# switch_eval_box_redo_v1.net
KiCad netlist of a schematic drawn in EAGLE
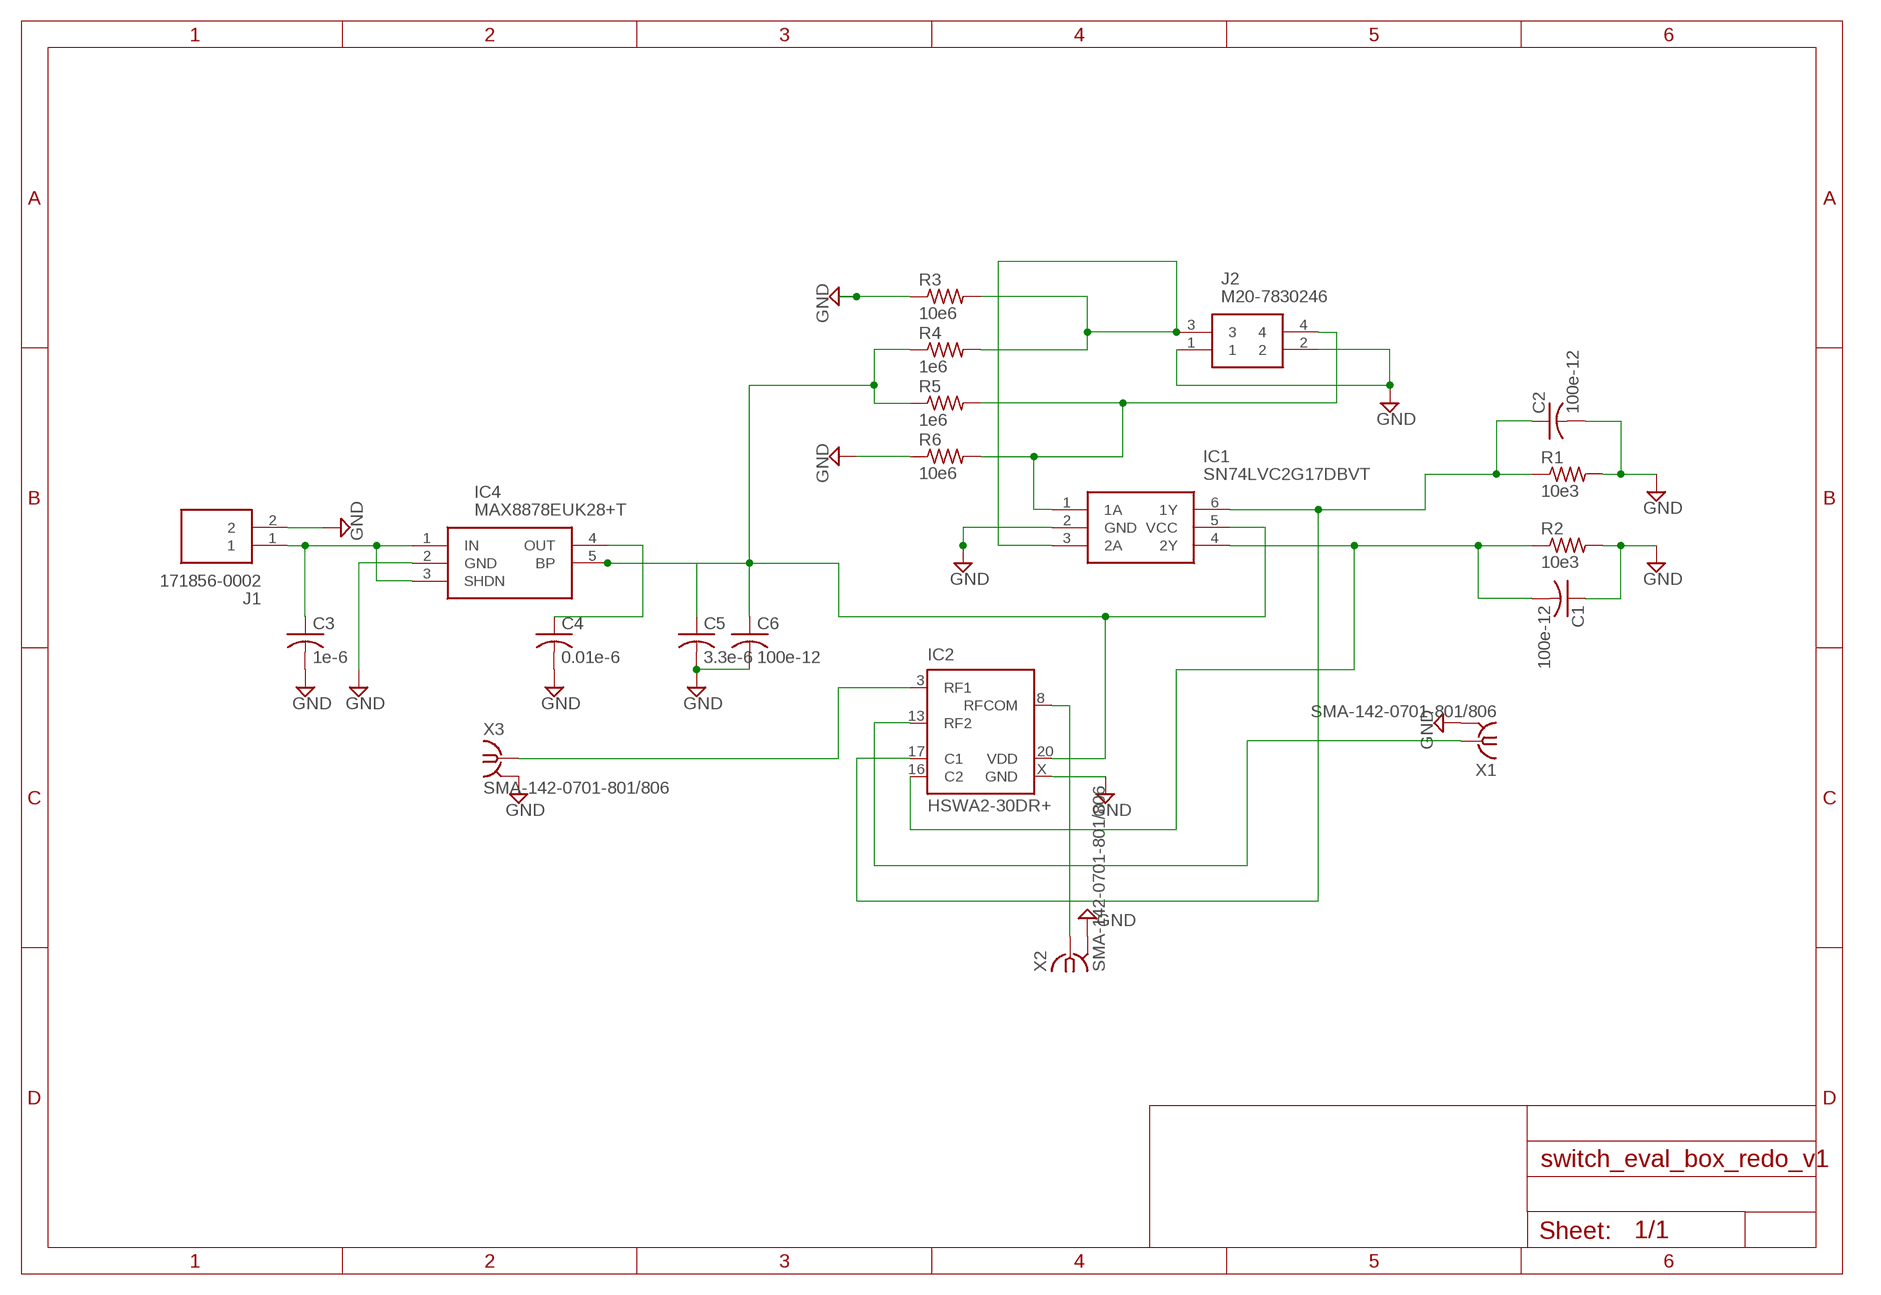
[diagram p0: schematic, sheet 1]

(export (version "E")
  (design (tool "Eeschema 10.0.6"))
  (components
    (comp (ref "C1")
      (value "100e-12")
      (footprint "eagle-import:C0603")
      (libsource (lib "eagle-import") (part "C-USC0603"))
    )
    (comp (ref "C2")
      (value "100e-12")
      (footprint "eagle-import:C0603")
      (libsource (lib "eagle-import") (part "C-USC0603"))
    )
    (comp (ref "C3")
      (value "1e-6")
      (footprint "eagle-import:C0603")
      (libsource (lib "eagle-import") (part "C-USC0603"))
    )
    (comp (ref "C4")
      (value "0.01e-6")
      (footprint "eagle-import:C0603")
      (libsource (lib "eagle-import") (part "C-USC0603"))
    )
    (comp (ref "C5")
      (value "3.3e-6")
      (footprint "eagle-import:C0603")
      (libsource (lib "eagle-import") (part "C-USC0603"))
    )
    (comp (ref "C6")
      (value "100e-12")
      (footprint "eagle-import:C0603")
      (libsource (lib "eagle-import") (part "C-USC0603"))
    )
    (comp (ref "IC1")
      (value "SN74LVC2G17DBVT")
      (footprint "eagle-import:SOT95P280X145-6N")
      (fields
        (field (name "MOUSER_PART_NUMBER") "595-SN74LVC2G17DBVT")
        (field (name "RS_PART_NUMBER") "6628944P")
      )
      (libsource (lib "eagle-import") (part "SN74LVC2G17DBVT"))
    )
    (comp (ref "IC2")
      (value "HSWA2-30DR+")
      (footprint "eagle-import:DG983-1")
      (libsource (lib "eagle-import") (part "HSWA2-30DR+"))
    )
    (comp (ref "IC4")
      (value "MAX8878EUK28+T")
      (footprint "eagle-import:SOT95P280X145-5N")
      (libsource (lib "eagle-import") (part "MAX8878EUK28+T"))
    )
    (comp (ref "J1")
      (value "171856-0002")
      (footprint "eagle-import:SHDR2W90P0X254_1X2_493X635X106")
      (fields
        (field (name "MOUSER_PART_NUMBER") "538-171856-0002")
        (field (name "RS_PART_NUMBER") "7922884P")
      )
      (libsource (lib "eagle-import") (part "171856-0002"))
    )
    (comp (ref "J2")
      (value "M20-7830246")
      (footprint "eagle-import:M207830246")
      (fields
        (field (name "MOUSER_PART_NUMBER") "855-M20-7830246")
        (field (name "RS_PART_NUMBER") "6816839P")
      )
      (libsource (lib "eagle-import") (part "M20-7830246"))
    )
    (comp (ref "R1")
      (value "10e3")
      (footprint "eagle-import:R0603")
      (libsource (lib "eagle-import") (part "R-US_R0603"))
    )
    (comp (ref "R2")
      (value "10e3")
      (footprint "eagle-import:R0603")
      (libsource (lib "eagle-import") (part "R-US_R0603"))
    )
    (comp (ref "R3")
      (value "10e6")
      (footprint "eagle-import:R0603")
      (libsource (lib "eagle-import") (part "R-US_R0603"))
    )
    (comp (ref "R4")
      (value "1e6")
      (footprint "eagle-import:R0603")
      (libsource (lib "eagle-import") (part "R-US_R0603"))
    )
    (comp (ref "R5")
      (value "1e6")
      (footprint "eagle-import:R0603")
      (libsource (lib "eagle-import") (part "R-US_R0603"))
    )
    (comp (ref "R6")
      (value "10e6")
      (footprint "eagle-import:R0603")
      (libsource (lib "eagle-import") (part "R-US_R0603"))
    )
    (comp (ref "X1")
      (value "SMA-142-0701-801/806")
      (footprint "eagle-import:J502-ND-142-0701-801_806")
      (fields (field (name "MF") "JOHNSON COMPONENTS") (field (name "MPN") "142-0701-801"))
      (libsource (lib "eagle-import") (part "SMA-142-0701-801/806"))
    )
    (comp (ref "X2")
      (value "SMA-142-0701-801/806")
      (footprint "eagle-import:J502-ND-142-0701-801_806")
      (fields (field (name "MF") "JOHNSON COMPONENTS") (field (name "MPN") "142-0701-801"))
      (libsource (lib "eagle-import") (part "SMA-142-0701-801/806"))
    )
    (comp (ref "X3")
      (value "SMA-142-0701-801/806")
      (footprint "eagle-import:J502-ND-142-0701-801_806")
      (fields (field (name "MF") "JOHNSON COMPONENTS") (field (name "MPN") "142-0701-801"))
      (libsource (lib "eagle-import") (part "SMA-142-0701-801/806"))
    )
  )
  (nets
    (net (code "1") (name "GND") (class "Default")
      (node (ref "C1") (pin "1") (pinfunction "1_1") (pintype "passive"))
      (node (ref "C2") (pin "2") (pinfunction "2_2") (pintype "passive"))
      (node (ref "C3") (pin "2") (pinfunction "2_2") (pintype "passive"))
      (node (ref "C4") (pin "2") (pinfunction "2_2") (pintype "passive"))
      (node (ref "C5") (pin "2") (pinfunction "2_2") (pintype "passive"))
      (node (ref "C6") (pin "2") (pinfunction "2_2") (pintype "passive"))
      (node (ref "IC1") (pin "2") (pinfunction "GND_2") (pintype "bidirectional"))
      (node (ref "IC2") (pin "X") (pinfunction "GND_X") (pintype "power_in"))
      (node (ref "IC4") (pin "2") (pinfunction "GND_2") (pintype "power_in"))
      (node (ref "J1") (pin "2") (pinfunction "2_2") (pintype "bidirectional"))
      (node (ref "J2") (pin "1") (pinfunction "1_1") (pintype "bidirectional"))
      (node (ref "J2") (pin "2") (pinfunction "2_2") (pintype "bidirectional"))
      (node (ref "R1") (pin "2") (pinfunction "2_2") (pintype "passive"))
      (node (ref "R2") (pin "2") (pinfunction "2_2") (pintype "passive"))
      (node (ref "R3") (pin "1") (pinfunction "1_1") (pintype "passive"))
      (node (ref "R6") (pin "1") (pinfunction "1_1") (pintype "passive"))
      (node (ref "X1") (pin "G@1") (pinfunction "2_G@1") (pintype "passive"))
      (node (ref "X1") (pin "G@2") (pinfunction "2_G@2") (pintype "passive"))
      (node (ref "X1") (pin "G@3") (pinfunction "2_G@3") (pintype "passive"))
      (node (ref "X1") (pin "G@4") (pinfunction "2_G@4") (pintype "passive"))
      (node (ref "X2") (pin "G@1") (pinfunction "2_G@1") (pintype "passive"))
      (node (ref "X2") (pin "G@2") (pinfunction "2_G@2") (pintype "passive"))
      (node (ref "X2") (pin "G@3") (pinfunction "2_G@3") (pintype "passive"))
      (node (ref "X2") (pin "G@4") (pinfunction "2_G@4") (pintype "passive"))
      (node (ref "X3") (pin "G@1") (pinfunction "2_G@1") (pintype "passive"))
      (node (ref "X3") (pin "G@2") (pinfunction "2_G@2") (pintype "passive"))
      (node (ref "X3") (pin "G@3") (pinfunction "2_G@3") (pintype "passive"))
      (node (ref "X3") (pin "G@4") (pinfunction "2_G@4") (pintype "passive"))
    )
    (net (code "2") (name "Net-(IC1-1A)") (class "Default")
      (node (ref "IC1") (pin "1") (pinfunction "1A_1") (pintype "bidirectional"))
      (node (ref "J2") (pin "4") (pinfunction "4_4") (pintype "bidirectional"))
      (node (ref "R5") (pin "2") (pinfunction "2_2") (pintype "passive"))
      (node (ref "R6") (pin "2") (pinfunction "2_2") (pintype "passive"))
    )
    (net (code "3") (name "Net-(IC1-1Y)") (class "Default")
      (node (ref "C2") (pin "1") (pinfunction "1_1") (pintype "passive"))
      (node (ref "IC1") (pin "6") (pinfunction "1Y_6") (pintype "bidirectional"))
      (node (ref "IC2") (pin "17") (pinfunction "C1_17") (pintype "passive"))
      (node (ref "R1") (pin "1") (pinfunction "1_1") (pintype "passive"))
    )
    (net (code "4") (name "Net-(IC1-2A)") (class "Default")
      (node (ref "IC1") (pin "3") (pinfunction "2A_3") (pintype "bidirectional"))
      (node (ref "J2") (pin "3") (pinfunction "3_3") (pintype "bidirectional"))
      (node (ref "R3") (pin "2") (pinfunction "2_2") (pintype "passive"))
      (node (ref "R4") (pin "2") (pinfunction "2_2") (pintype "passive"))
    )
    (net (code "5") (name "Net-(IC1-2Y)") (class "Default")
      (node (ref "C1") (pin "2") (pinfunction "2_2") (pintype "passive"))
      (node (ref "IC1") (pin "4") (pinfunction "2Y_4") (pintype "bidirectional"))
      (node (ref "IC2") (pin "16") (pinfunction "C2_16") (pintype "passive"))
      (node (ref "R2") (pin "1") (pinfunction "1_1") (pintype "passive"))
    )
    (net (code "6") (name "Net-(IC1-VCC)") (class "Default")
      (node (ref "C5") (pin "1") (pinfunction "1_1") (pintype "passive"))
      (node (ref "C6") (pin "1") (pinfunction "1_1") (pintype "passive"))
      (node (ref "IC1") (pin "5") (pinfunction "VCC_5") (pintype "bidirectional"))
      (node (ref "IC2") (pin "20") (pinfunction "VDD_20") (pintype "input"))
      (node (ref "IC4") (pin "5") (pinfunction "BP_5") (pintype "bidirectional"))
      (node (ref "R4") (pin "1") (pinfunction "1_1") (pintype "passive"))
      (node (ref "R5") (pin "1") (pinfunction "1_1") (pintype "passive"))
    )
    (net (code "7") (name "Net-(IC2A-RF1)") (class "Default")
      (node (ref "IC2") (pin "3") (pinfunction "RF1_3") (pintype "passive"))
      (node (ref "X3") (pin "1") (pinfunction "1_1") (pintype "passive"))
    )
    (net (code "8") (name "Net-(IC2A-RF2)") (class "Default")
      (node (ref "IC2") (pin "13") (pinfunction "RF2_13") (pintype "passive"))
      (node (ref "X1") (pin "1") (pinfunction "1_1") (pintype "passive"))
    )
    (net (code "9") (name "Net-(IC2A-RFCOM)") (class "Default")
      (node (ref "IC2") (pin "8") (pinfunction "RFCOM_8") (pintype "passive"))
      (node (ref "X2") (pin "1") (pinfunction "1_1") (pintype "passive"))
    )
    (net (code "10") (name "Net-(IC4-IN)") (class "Default")
      (node (ref "C3") (pin "1") (pinfunction "1_1") (pintype "passive"))
      (node (ref "IC4") (pin "1") (pinfunction "IN_1") (pintype "input"))
      (node (ref "IC4") (pin "3") (pinfunction "SHDN_3") (pintype "bidirectional"))
      (node (ref "J1") (pin "1") (pinfunction "1_1") (pintype "bidirectional"))
    )
    (net (code "11") (name "Net-(IC4-OUT)") (class "Default")
      (node (ref "C4") (pin "1") (pinfunction "1_1") (pintype "passive"))
      (node (ref "IC4") (pin "4") (pinfunction "OUT_4") (pintype "output"))
    )
  )
)
